# MB1136.net
KiCad netlist of a schematic drawn in Altium Designer
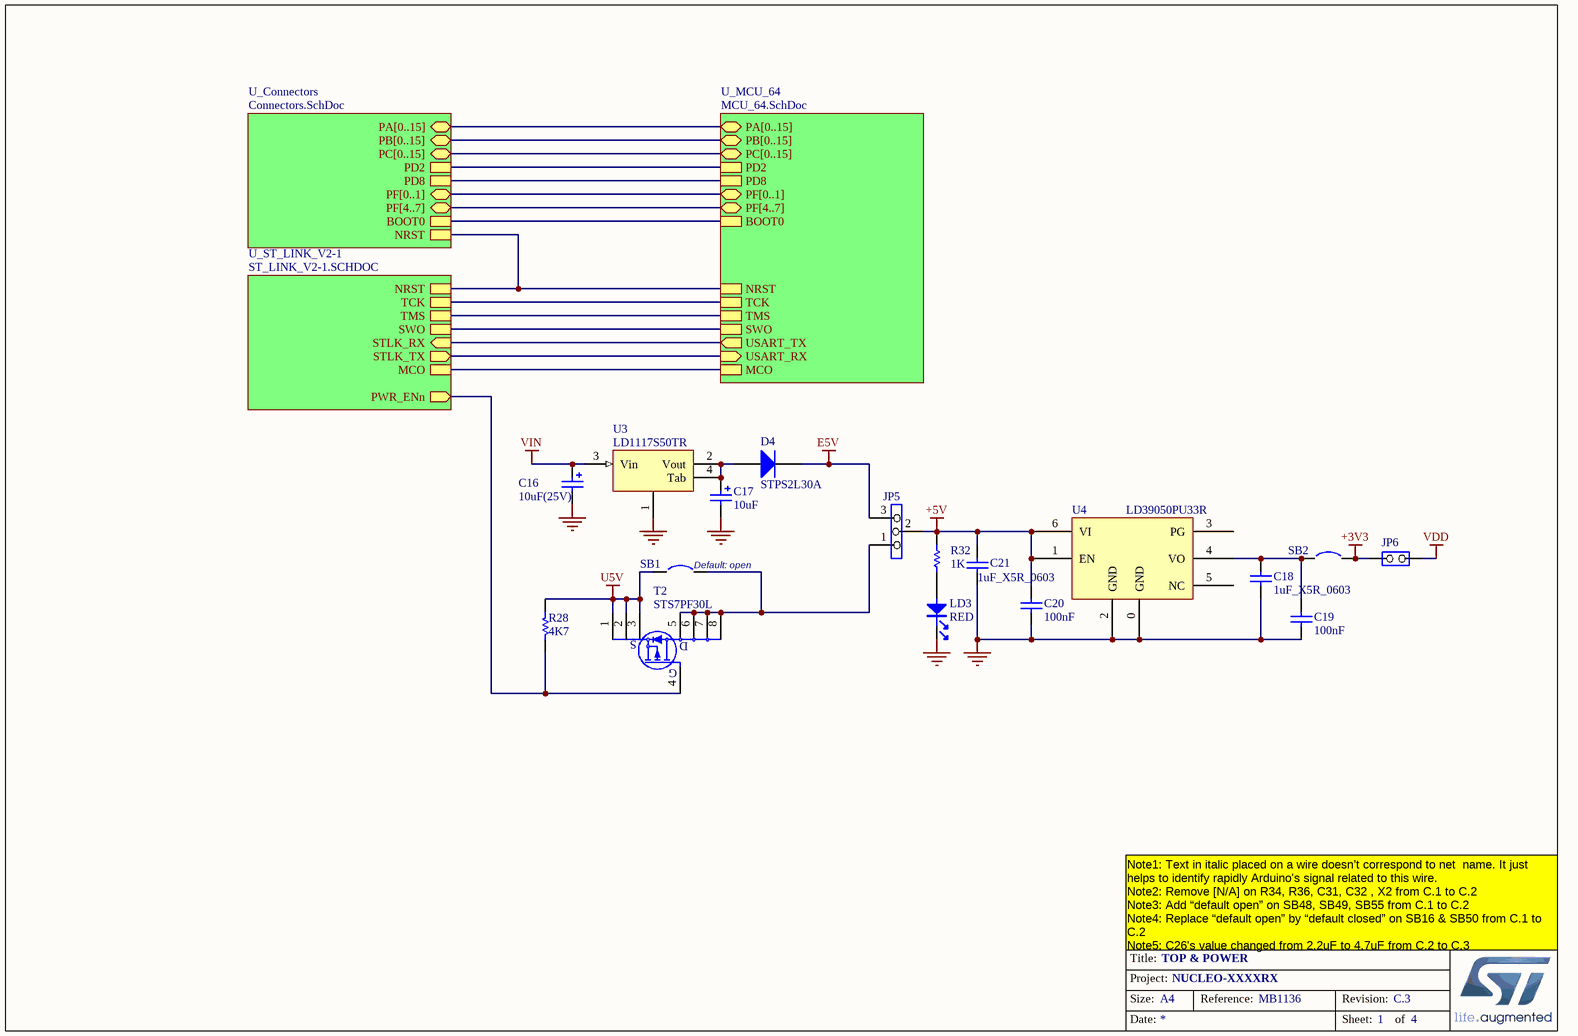
[diagram p0: MB1136.SchDoc]

(export (version "E")
  (design (tool "Eeschema 10.0.6"))
  (components
    (comp (ref "C16")
      (value "10uF(25V)")
      (footprint "TAN-B")
      (description "Polarized Capacitor (Radial)")
      (fields (field (name "PUBLISHER") "Altium Limited"))
      (libsource (lib "Miscellaneous Devices") (part "Cap Pol1"))
    )
    (comp (ref "C17")
      (value "10uF")
      (footprint "TAN-A")
      (description "Polarized Capacitor (Radial)")
      (fields (field (name "PUBLISHER") "Altium Limited"))
      (libsource (lib "Miscellaneous Devices") (part "Cap Pol1"))
    )
    (comp (ref "C18")
      (value "1uF_X5R_0603")
      (footprint "0603C")
      (description "0603  X5R 1µF")
      (fields (field (name "TOLERANCE") "10%"))
      (libsource (lib "MB963_1") (part "CAP SMD 0603  X5R 1µF 25V 10%"))
    )
    (comp (ref "C19")
      (value "100nF")
      (footprint "0603C")
      (description "Capacitor 0402 / 0603 / 0805")
      (libsource (lib "MCD_TOOLS") (part "Capacitor_ST"))
    )
    (comp (ref "C20")
      (value "100nF")
      (footprint "0603C")
      (description "Capacitor 0402 / 0603 / 0805")
      (libsource (lib "MCD_TOOLS") (part "Capacitor_ST"))
    )
    (comp (ref "C21")
      (value "1uF_X5R_0603")
      (footprint "0603C")
      (description "0603  X5R 1µF")
      (fields (field (name "TOLERANCE") "10%"))
      (libsource (lib "MB963_1") (part "CAP SMD 0603  X5R 1µF 25V 10%"))
    )
    (comp (ref "D4") (value "STPS2L30A") (footprint "SMA") (libsource (lib "Nucleo_64") (part "STPS2L30A")))
    (comp (ref "JP5") (value "~") (footprint "SIP3") (libsource (lib "STR910_SCHLIB") (part "Jumper3")))
    (comp (ref "JP6") (value "~") (footprint "SIP2/2.54") (libsource (lib "*") (part "JP2")))
    (comp (ref "LD3") (value "RED") (footprint "0603D") (libsource (lib "MB963_1") (part "PHOTO")))
    (comp (ref "R28")
      (value "4K7")
      (footprint "0603R")
      (description "Resistor")
      (fields (field (name "PUBLISHER") "Altium Limited"))
      (libsource (lib "*") (part "Res1"))
    )
    (comp (ref "R32")
      (value "1K")
      (footprint "0603R")
      (description "Resistor 0402 or 0603 or 0805")
      (libsource (lib "MCD_TOOLS") (part "Resistor_ST"))
    )
    (comp (ref "SB1")
      (value "Circuit Breaker")
      (footprint "JP2_SMD")
      (fields (field (name "PUBLISHER") "Altium Limited"))
      (libsource (lib "MCD_TOOLS") (part "Circuit Breaker"))
    )
    (comp (ref "SB2")
      (value "Circuit Breaker")
      (footprint "JP2_SMD")
      (fields (field (name "PUBLISHER") "Altium Limited"))
      (libsource (lib "MCD_TOOLS") (part "Circuit Breaker"))
    )
    (comp (ref "T2") (value "STS7PF30L") (footprint "SO8") (libsource (lib "Nucleo_64") (part "STS7PF30L")))
    (comp (ref "U3") (value "LD1117S50TR") (footprint "SOT-223") (libsource (lib "mb1045") (part "LD1117")))
    (comp (ref "U4")
      (value "LD39050PU33R")
      (footprint "DFN6(3X3)")
      (libsource (lib "Nucleo_64") (part "LD39050P"))
    )
  )
  (nets
    (net (code "1") (name "+3V3") (class "Default")
      (node (ref "JP6") (pin "1") (pinfunction "COMMON_1") (pintype "passive"))
      (node (ref "SB2") (pin "2") (pinfunction "2_2") (pintype "passive"))
    )
    (net (code "2") (name "+5V") (class "Default")
      (node (ref "C20") (pin "2") (pinfunction "2_2") (pintype "passive"))
      (node (ref "C21") (pin "1") (pinfunction "1_1") (pintype "passive"))
      (node (ref "JP5") (pin "2") (pintype "passive"))
      (node (ref "R32") (pin "2") (pinfunction "2_2") (pintype "passive"))
      (node (ref "U4") (pin "1") (pinfunction "EN_1") (pintype "passive"))
      (node (ref "U4") (pin "6") (pinfunction "VI_6") (pintype "passive"))
    )
    (net (code "13") (name "/PWR_ENn") (class "Default")
      (node (ref "R28") (pin "2") (pinfunction "2_2") (pintype "passive"))
      (node (ref "T2") (pin "4") (pinfunction "G_4") (pintype "passive"))
    )
    (net (code "19") (name "E5V") (class "Default")
      (node (ref "D4") (pin "2") (pinfunction "K_2") (pintype "passive"))
      (node (ref "JP5") (pin "3") (pintype "passive"))
    )
    (net (code "20") (name "GND") (class "Default")
      (node (ref "C16") (pin "2") (pinfunction "2_2") (pintype "passive"))
      (node (ref "C17") (pin "2") (pinfunction "2_2") (pintype "passive"))
      (node (ref "C18") (pin "2") (pinfunction "2_2") (pintype "passive"))
      (node (ref "C19") (pin "1") (pinfunction "1_1") (pintype "passive"))
      (node (ref "C20") (pin "1") (pinfunction "1_1") (pintype "passive"))
      (node (ref "C21") (pin "2") (pinfunction "2_2") (pintype "passive"))
      (node (ref "LD3") (pin "2") (pintype "passive"))
      (node (ref "U3") (pin "1") (pintype "passive"))
      (node (ref "U4") (pin "0") (pinfunction "GND_0") (pintype "passive"))
      (node (ref "U4") (pin "2") (pinfunction "GND_2") (pintype "passive"))
    )
    (net (code "21") (name "Net-(D4-A)") (class "Default")
      (node (ref "C17") (pin "1") (pinfunction "1_1") (pintype "passive"))
      (node (ref "D4") (pin "1") (pinfunction "A_1") (pintype "passive"))
      (node (ref "U3") (pin "2") (pinfunction "Vout_2") (pintype "power_in"))
      (node (ref "U3") (pin "4") (pinfunction "Tab_4") (pintype "power_in"))
    )
    (net (code "22") (name "Net-(JP5-Pad1)") (class "Default")
      (node (ref "JP5") (pin "1") (pintype "passive"))
      (node (ref "SB1") (pin "2") (pinfunction "2_2") (pintype "passive"))
      (node (ref "T2") (pin "5") (pinfunction "D_5") (pintype "passive"))
      (node (ref "T2") (pin "6") (pinfunction "D_6") (pintype "passive"))
      (node (ref "T2") (pin "7") (pinfunction "D_7") (pintype "passive"))
      (node (ref "T2") (pin "8") (pinfunction "D_8") (pintype "passive"))
    )
    (net (code "23") (name "Net-(LD3-Pad1)") (class "Default")
      (node (ref "LD3") (pin "1") (pintype "passive"))
      (node (ref "R32") (pin "1") (pinfunction "1_1") (pintype "passive"))
    )
    (net (code "24") (name "Net-(U4-VO)") (class "Default")
      (node (ref "C18") (pin "1") (pinfunction "1_1") (pintype "passive"))
      (node (ref "C19") (pin "2") (pinfunction "2_2") (pintype "passive"))
      (node (ref "SB2") (pin "1") (pinfunction "1_1") (pintype "passive"))
      (node (ref "U4") (pin "4") (pinfunction "VO_4") (pintype "passive"))
    )
    (net (code "25") (name "U5V") (class "Default")
      (node (ref "R28") (pin "1") (pinfunction "1_1") (pintype "passive"))
      (node (ref "SB1") (pin "1") (pinfunction "1_1") (pintype "passive"))
      (node (ref "T2") (pin "1") (pinfunction "S_1") (pintype "passive"))
      (node (ref "T2") (pin "2") (pinfunction "S_2") (pintype "passive"))
      (node (ref "T2") (pin "3") (pinfunction "S_3") (pintype "passive"))
    )
    (net (code "26") (name "VDD") (class "Default")
      (node (ref "JP6") (pin "2") (pinfunction "NO_2") (pintype "passive"))
    )
    (net (code "27") (name "VIN") (class "Default")
      (node (ref "C16") (pin "1") (pinfunction "1_1") (pintype "passive"))
      (node (ref "U3") (pin "3") (pinfunction "Vin_3") (pintype "input"))
    )
    (net (code "28") (name "unconnected-(U4-NC-Pad5)") (class "Default")
      (node (ref "U4") (pin "5") (pinfunction "NC_5") (pintype "passive"))
    )
    (net (code "29") (name "unconnected-(U4-PG-Pad3)") (class "Default")
      (node (ref "U4") (pin "3") (pinfunction "PG_3") (pintype "passive"))
    )
  )
)
